# Emat.net
KiCad netlist of a schematic drawn in EAGLE
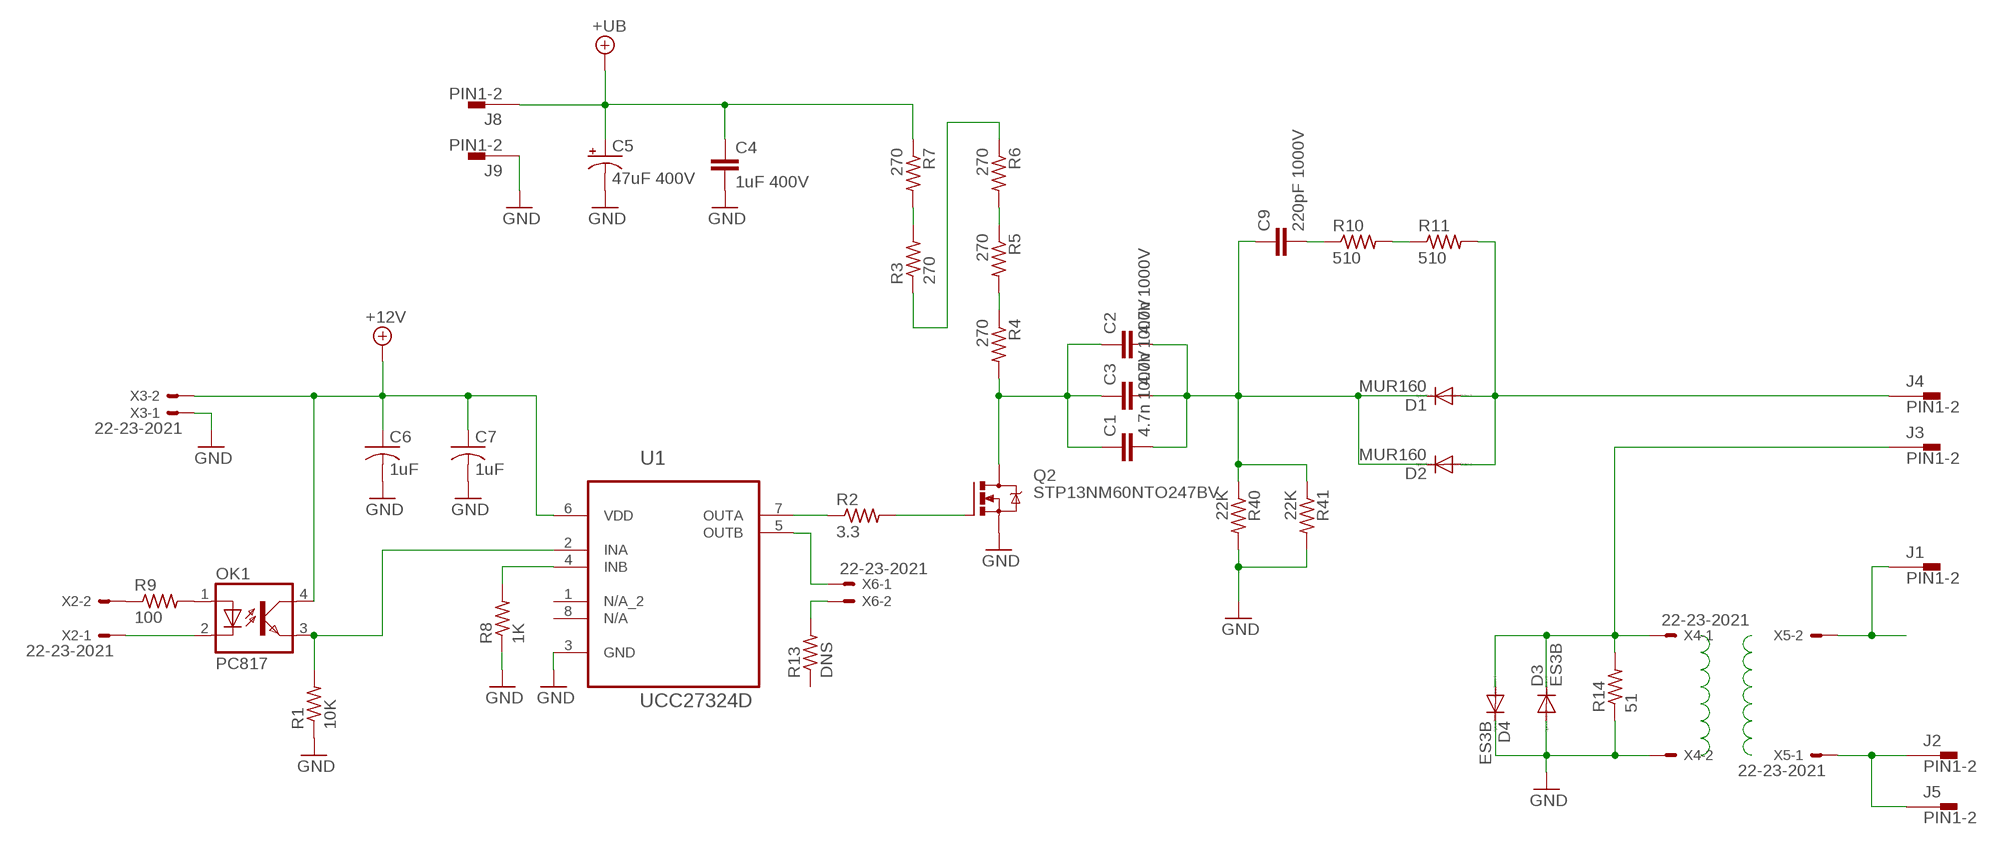
[diagram p0: schematic, sheet 1]

(export (version "E")
  (design (tool "Eeschema 10.0.6"))
  (components
    (comp (ref "C1")
      (value "4.7n 1000V")
      (footprint "eagle-import:C10B4")
      (libsource (lib "eagle-import") (part "C10/4"))
    )
    (comp (ref "C2")
      (value "4.7n 1000V")
      (footprint "eagle-import:C10B4")
      (libsource (lib "eagle-import") (part "C10/4"))
    )
    (comp (ref "C3")
      (value "4.7n 1000V")
      (footprint "eagle-import:C10B4")
      (libsource (lib "eagle-import") (part "C10/4"))
    )
    (comp (ref "C4")
      (value "1uF 400V")
      (footprint "eagle-import:C27.5B13")
      (libsource (lib "eagle-import") (part "C27/13"))
    )
    (comp (ref "C5")
      (value "47uF 400V")
      (footprint "eagle-import:SANYO-OSCON_G")
      (libsource (lib "eagle-import") (part "CPOL-USSANYO_G"))
    )
    (comp (ref "C6")
      (value "1uF")
      (footprint "eagle-import:C0805")
      (libsource (lib "eagle-import") (part "C-USC0805"))
    )
    (comp (ref "C7")
      (value "1uF")
      (footprint "eagle-import:C0805")
      (libsource (lib "eagle-import") (part "C-USC0805"))
    )
    (comp (ref "C9")
      (value "220pF 1000V")
      (footprint "eagle-import:C075-042X103")
      (libsource (lib "eagle-import") (part "C-EU075-042X103"))
    )
    (comp (ref "D1")
      (value "MUR160")
      (footprint "eagle-import:DO41-10")
      (libsource (lib "eagle-import") (part "MUR160"))
    )
    (comp (ref "D2")
      (value "MUR160")
      (footprint "eagle-import:DO41-10")
      (libsource (lib "eagle-import") (part "MUR160"))
    )
    (comp (ref "D3")
      (value "ES3B")
      (footprint "eagle-import:SMC")
      (libsource (lib "eagle-import") (part "DIODE-SMC"))
    )
    (comp (ref "D4")
      (value "ES3B")
      (footprint "eagle-import:SMC")
      (libsource (lib "eagle-import") (part "DIODE-SMC"))
    )
    (comp (ref "J1")
      (value "PIN1-2")
      (footprint "eagle-import:62221")
      (fields (field (name "MF") "TYCO ELECTRONICS") (field (name "MPN") "62221-1"))
      (libsource (lib "eagle-import") (part "PIN1-2"))
    )
    (comp (ref "J2")
      (value "PIN1-2")
      (footprint "eagle-import:62221")
      (fields (field (name "MF") "TYCO ELECTRONICS") (field (name "MPN") "62221-1"))
      (libsource (lib "eagle-import") (part "PIN1-2"))
    )
    (comp (ref "J3")
      (value "PIN1-2")
      (footprint "eagle-import:62221")
      (fields (field (name "MF") "TYCO ELECTRONICS") (field (name "MPN") "62221-1"))
      (libsource (lib "eagle-import") (part "PIN1-2"))
    )
    (comp (ref "J4")
      (value "PIN1-2")
      (footprint "eagle-import:62221")
      (fields (field (name "MF") "TYCO ELECTRONICS") (field (name "MPN") "62221-1"))
      (libsource (lib "eagle-import") (part "PIN1-2"))
    )
    (comp (ref "J5")
      (value "PIN1-2")
      (footprint "eagle-import:62221")
      (fields (field (name "MF") "TYCO ELECTRONICS") (field (name "MPN") "62221-1"))
      (libsource (lib "eagle-import") (part "PIN1-2"))
    )
    (comp (ref "J8")
      (value "PIN1-2")
      (footprint "eagle-import:62221")
      (fields (field (name "MF") "TYCO ELECTRONICS") (field (name "MPN") "62221-1"))
      (libsource (lib "eagle-import") (part "PIN1-2"))
    )
    (comp (ref "J9")
      (value "PIN1-2")
      (footprint "eagle-import:62221")
      (fields (field (name "MF") "TYCO ELECTRONICS") (field (name "MPN") "62221-1"))
      (libsource (lib "eagle-import") (part "PIN1-2"))
    )
    (comp (ref "OK1")
      (value "PC817")
      (footprint "eagle-import:DIL04")
      (fields (field (name "MPN") "PC817X4J000F"))
      (libsource (lib "eagle-import") (part "PC817"))
    )
    (comp (ref "Q2")
      (value "STP13NM60NTO247BV")
      (footprint "eagle-import:TO247BV")
      (libsource (lib "eagle-import") (part "STP13NM60NTO247BV"))
    )
    (comp (ref "R1")
      (value "10K")
      (footprint "eagle-import:R1206")
      (libsource (lib "eagle-import") (part "R-US_R1206"))
    )
    (comp (ref "R2")
      (value "3.3")
      (footprint "eagle-import:R1206")
      (libsource (lib "eagle-import") (part "R-US_R1206"))
    )
    (comp (ref "R3")
      (value "270")
      (footprint "eagle-import:R2512")
      (libsource (lib "eagle-import") (part "resistor_R-US_R2512"))
    )
    (comp (ref "R4")
      (value "270")
      (footprint "eagle-import:R2512")
      (libsource (lib "eagle-import") (part "resistor_R-US_R2512"))
    )
    (comp (ref "R5")
      (value "270")
      (footprint "eagle-import:R2512")
      (libsource (lib "eagle-import") (part "resistor_R-US_R2512"))
    )
    (comp (ref "R6")
      (value "270")
      (footprint "eagle-import:R2512")
      (libsource (lib "eagle-import") (part "resistor_R-US_R2512"))
    )
    (comp (ref "R7")
      (value "270")
      (footprint "eagle-import:R2512")
      (libsource (lib "eagle-import") (part "resistor_R-US_R2512"))
    )
    (comp (ref "R8")
      (value "1K")
      (footprint "eagle-import:R1206")
      (libsource (lib "eagle-import") (part "R-US_R1206"))
    )
    (comp (ref "R9")
      (value "100")
      (footprint "eagle-import:R1206")
      (libsource (lib "eagle-import") (part "R-US_R1206"))
    )
    (comp (ref "R10")
      (value "510")
      (footprint "eagle-import:R1206")
      (libsource (lib "eagle-import") (part "R-US_R1206"))
    )
    (comp (ref "R11")
      (value "510")
      (footprint "eagle-import:R1206")
      (libsource (lib "eagle-import") (part "R-US_R1206"))
    )
    (comp (ref "R13")
      (value "DNS")
      (footprint "eagle-import:R1206")
      (libsource (lib "eagle-import") (part "R-US_R1206"))
    )
    (comp (ref "R14")
      (value "51")
      (footprint "eagle-import:R1206")
      (libsource (lib "eagle-import") (part "R-US_R1206"))
    )
    (comp (ref "R40")
      (value "22K")
      (footprint "eagle-import:R2512")
      (libsource (lib "eagle-import") (part "R-US_R2512"))
    )
    (comp (ref "R41")
      (value "22K")
      (footprint "eagle-import:R2512")
      (libsource (lib "eagle-import") (part "R-US_R2512"))
    )
    (comp (ref "U1")
      (value "UCC27324D")
      (footprint "eagle-import:SOIC127P600X175-8N")
      (libsource (lib "eagle-import") (part "UCC27324D"))
    )
    (comp (ref "X2")
      (value "22-23-2021")
      (footprint "eagle-import:22-23-2021")
      (fields (field (name "MF") "MOLEX"))
      (libsource (lib "eagle-import") (part "22-23-2021"))
    )
    (comp (ref "X3")
      (value "22-23-2021")
      (footprint "eagle-import:22-23-2021")
      (fields (field (name "MF") "MOLEX"))
      (libsource (lib "eagle-import") (part "22-23-2021"))
    )
    (comp (ref "X4")
      (value "22-23-2021")
      (footprint "eagle-import:22-23-2021")
      (fields (field (name "MF") "MOLEX"))
      (libsource (lib "eagle-import") (part "22-23-2021"))
    )
    (comp (ref "X5")
      (value "22-23-2021")
      (footprint "eagle-import:22-23-2021")
      (fields (field (name "MF") "MOLEX"))
      (libsource (lib "eagle-import") (part "22-23-2021"))
    )
    (comp (ref "X6")
      (value "22-23-2021")
      (footprint "eagle-import:22-23-2021")
      (fields (field (name "MF") "MOLEX"))
      (libsource (lib "eagle-import") (part "22-23-2021"))
    )
  )
  (nets
    (net (code "1") (name "+12V") (class "Default")
      (node (ref "C6") (pin "1") (pinfunction "1_1") (pintype "passive"))
      (node (ref "C7") (pin "1") (pinfunction "1_1") (pintype "passive"))
      (node (ref "OK1") (pin "4") (pinfunction "COL_4") (pintype "passive"))
      (node (ref "U1") (pin "6") (pinfunction "VDD_6") (pintype "power_in"))
      (node (ref "X3") (pin "2") (pinfunction "S_2") (pintype "passive"))
    )
    (net (code "2") (name "+UB") (class "Default")
      (node (ref "C4") (pin "1") (pinfunction "1_1") (pintype "passive"))
      (node (ref "C5") (pin "+") (pinfunction "+_+") (pintype "passive"))
      (node (ref "J8") (pin "1") (pinfunction "1_1") (pintype "passive"))
      (node (ref "R7") (pin "1") (pinfunction "1_1") (pintype "passive"))
    )
    (net (code "4") (name "GND") (class "Default")
      (node (ref "C4") (pin "2") (pinfunction "2_2") (pintype "passive"))
      (node (ref "C5") (pin "-") (pinfunction "-_-") (pintype "passive"))
      (node (ref "C6") (pin "2") (pinfunction "2_2") (pintype "passive"))
      (node (ref "C7") (pin "2") (pinfunction "2_2") (pintype "passive"))
      (node (ref "D3") (pin "A") (pinfunction "A_A") (pintype "passive"))
      (node (ref "D4") (pin "C") (pinfunction "C_C") (pintype "passive"))
      (node (ref "J9") (pin "1") (pinfunction "1_1") (pintype "passive"))
      (node (ref "Q2") (pin "S") (pinfunction "S_S") (pintype "passive"))
      (node (ref "R1") (pin "1") (pinfunction "1_1") (pintype "passive"))
      (node (ref "R14") (pin "1") (pinfunction "1_1") (pintype "passive"))
      (node (ref "R40") (pin "2") (pinfunction "2_2") (pintype "passive"))
      (node (ref "R41") (pin "2") (pinfunction "2_2") (pintype "passive"))
      (node (ref "R8") (pin "1") (pinfunction "1_1") (pintype "passive"))
      (node (ref "U1") (pin "3") (pinfunction "GND_3") (pintype "passive"))
      (node (ref "X3") (pin "1") (pinfunction "S_1") (pintype "passive"))
      (node (ref "X4") (pin "2") (pinfunction "S_2") (pintype "passive"))
    )
    (net (code "5") (name "Net-(C1-Pad1)") (class "Default")
      (node (ref "C1") (pin "1") (pinfunction "1_1") (pintype "passive"))
      (node (ref "C2") (pin "1") (pinfunction "1_1") (pintype "passive"))
      (node (ref "C3") (pin "1") (pinfunction "1_1") (pintype "passive"))
      (node (ref "Q2") (pin "D") (pinfunction "D_D") (pintype "passive"))
      (node (ref "R4") (pin "2") (pinfunction "2_2") (pintype "passive"))
    )
    (net (code "6") (name "Net-(C1-Pad2)") (class "Default")
      (node (ref "C1") (pin "2") (pinfunction "2_2") (pintype "passive"))
      (node (ref "C2") (pin "2") (pinfunction "2_2") (pintype "passive"))
      (node (ref "C3") (pin "2") (pinfunction "2_2") (pintype "passive"))
      (node (ref "C9") (pin "1") (pinfunction "1_1") (pintype "passive"))
      (node (ref "D1") (pin "C") (pinfunction "C_C") (pintype "passive"))
      (node (ref "D2") (pin "C") (pinfunction "C_C") (pintype "passive"))
      (node (ref "R40") (pin "1") (pinfunction "1_1") (pintype "passive"))
      (node (ref "R41") (pin "1") (pinfunction "1_1") (pintype "passive"))
    )
    (net (code "7") (name "Net-(C9-Pad2)") (class "Default")
      (node (ref "C9") (pin "2") (pinfunction "2_2") (pintype "passive"))
      (node (ref "R10") (pin "1") (pinfunction "1_1") (pintype "passive"))
    )
    (net (code "8") (name "Net-(D1-PadA)") (class "Default")
      (node (ref "D1") (pin "A") (pinfunction "A_A") (pintype "passive"))
      (node (ref "D2") (pin "A") (pinfunction "A_A") (pintype "passive"))
      (node (ref "J4") (pin "1") (pinfunction "1_1") (pintype "passive"))
      (node (ref "R11") (pin "2") (pinfunction "2_2") (pintype "passive"))
    )
    (net (code "9") (name "Net-(OK1-A)") (class "Default")
      (node (ref "OK1") (pin "1") (pinfunction "A_1") (pintype "passive"))
      (node (ref "R9") (pin "2") (pinfunction "2_2") (pintype "passive"))
    )
    (net (code "10") (name "Net-(OK1-C)") (class "Default")
      (node (ref "OK1") (pin "2") (pinfunction "C_2") (pintype "passive"))
      (node (ref "X2") (pin "1") (pinfunction "S_1") (pintype "passive"))
    )
    (net (code "11") (name "Net-(OK1-EMIT)") (class "Default")
      (node (ref "OK1") (pin "3") (pinfunction "EMIT_3") (pintype "passive"))
      (node (ref "R1") (pin "2") (pinfunction "2_2") (pintype "passive"))
      (node (ref "U1") (pin "2") (pinfunction "INA_2") (pintype "input"))
    )
    (net (code "12") (name "Net-(Q2-PadG)") (class "Default")
      (node (ref "Q2") (pin "G") (pinfunction "G_G") (pintype "passive"))
      (node (ref "R2") (pin "2") (pinfunction "2_2") (pintype "passive"))
    )
    (net (code "13") (name "Net-(R3-Pad1)") (class "Default")
      (node (ref "R3") (pin "1") (pinfunction "1_1") (pintype "passive"))
      (node (ref "R6") (pin "1") (pinfunction "1_1") (pintype "passive"))
    )
    (net (code "14") (name "Net-(R3-Pad2)") (class "Default")
      (node (ref "R3") (pin "2") (pinfunction "2_2") (pintype "passive"))
      (node (ref "R7") (pin "2") (pinfunction "2_2") (pintype "passive"))
    )
    (net (code "15") (name "Net-(R4-Pad1)") (class "Default")
      (node (ref "R4") (pin "1") (pinfunction "1_1") (pintype "passive"))
      (node (ref "R5") (pin "2") (pinfunction "2_2") (pintype "passive"))
    )
    (net (code "16") (name "Net-(R5-Pad1)") (class "Default")
      (node (ref "R5") (pin "1") (pinfunction "1_1") (pintype "passive"))
      (node (ref "R6") (pin "2") (pinfunction "2_2") (pintype "passive"))
    )
    (net (code "17") (name "Net-(R10-Pad2)") (class "Default")
      (node (ref "R10") (pin "2") (pinfunction "2_2") (pintype "passive"))
      (node (ref "R11") (pin "1") (pinfunction "1_1") (pintype "passive"))
    )
    (net (code "18") (name "Net-(U1-INB)") (class "Default")
      (node (ref "R8") (pin "2") (pinfunction "2_2") (pintype "passive"))
      (node (ref "U1") (pin "4") (pinfunction "INB_4") (pintype "input"))
    )
    (net (code "19") (name "Net-(U1-OUTA)") (class "Default")
      (node (ref "R2") (pin "1") (pinfunction "1_1") (pintype "passive"))
      (node (ref "U1") (pin "7") (pinfunction "OUTA_7") (pintype "output"))
    )
    (net (code "20") (name "Net-(U1-OUTB)") (class "Default")
      (node (ref "U1") (pin "5") (pinfunction "OUTB_5") (pintype "output"))
      (node (ref "X6") (pin "1") (pinfunction "S_1") (pintype "passive"))
    )
    (net (code "21") (name "Net-(X2B-S)") (class "Default")
      (node (ref "R9") (pin "1") (pinfunction "1_1") (pintype "passive"))
      (node (ref "X2") (pin "2") (pinfunction "S_2") (pintype "passive"))
    )
    (net (code "22") (name "Net-(X4A-S)") (class "Default")
      (node (ref "D3") (pin "C") (pinfunction "C_C") (pintype "passive"))
      (node (ref "D4") (pin "A") (pinfunction "A_A") (pintype "passive"))
      (node (ref "J3") (pin "1") (pinfunction "1_1") (pintype "passive"))
      (node (ref "R14") (pin "2") (pinfunction "2_2") (pintype "passive"))
      (node (ref "X4") (pin "1") (pinfunction "S_1") (pintype "passive"))
    )
    (net (code "23") (name "Net-(X5A-S)") (class "Default")
      (node (ref "J2") (pin "1") (pinfunction "1_1") (pintype "passive"))
      (node (ref "J5") (pin "1") (pinfunction "1_1") (pintype "passive"))
      (node (ref "X5") (pin "1") (pinfunction "S_1") (pintype "passive"))
    )
    (net (code "24") (name "Net-(X5B-S)") (class "Default")
      (node (ref "J1") (pin "1") (pinfunction "1_1") (pintype "passive"))
      (node (ref "X5") (pin "2") (pinfunction "S_2") (pintype "passive"))
    )
    (net (code "25") (name "Net-(X6B-S)") (class "Default")
      (node (ref "R13") (pin "2") (pinfunction "2_2") (pintype "passive"))
      (node (ref "X6") (pin "2") (pinfunction "S_2") (pintype "passive"))
    )
    (net (code "26") (name "unconnected-(R13-Pad1)") (class "Default")
      (node (ref "R13") (pin "1") (pinfunction "1_1") (pintype "passive"))
    )
    (net (code "27") (name "unconnected-(U1-N{slash}A-Pad8)") (class "Default")
      (node (ref "U1") (pin "8") (pinfunction "N/A_8") (pintype "no_connect"))
    )
    (net (code "28") (name "unconnected-(U1-N{slash}A_2-Pad1)") (class "Default")
      (node (ref "U1") (pin "1") (pinfunction "N/A_2_1") (pintype "no_connect"))
    )
  )
)
